# ai_hub_usb.net
KiCad netlist of a schematic drawn in EAGLE
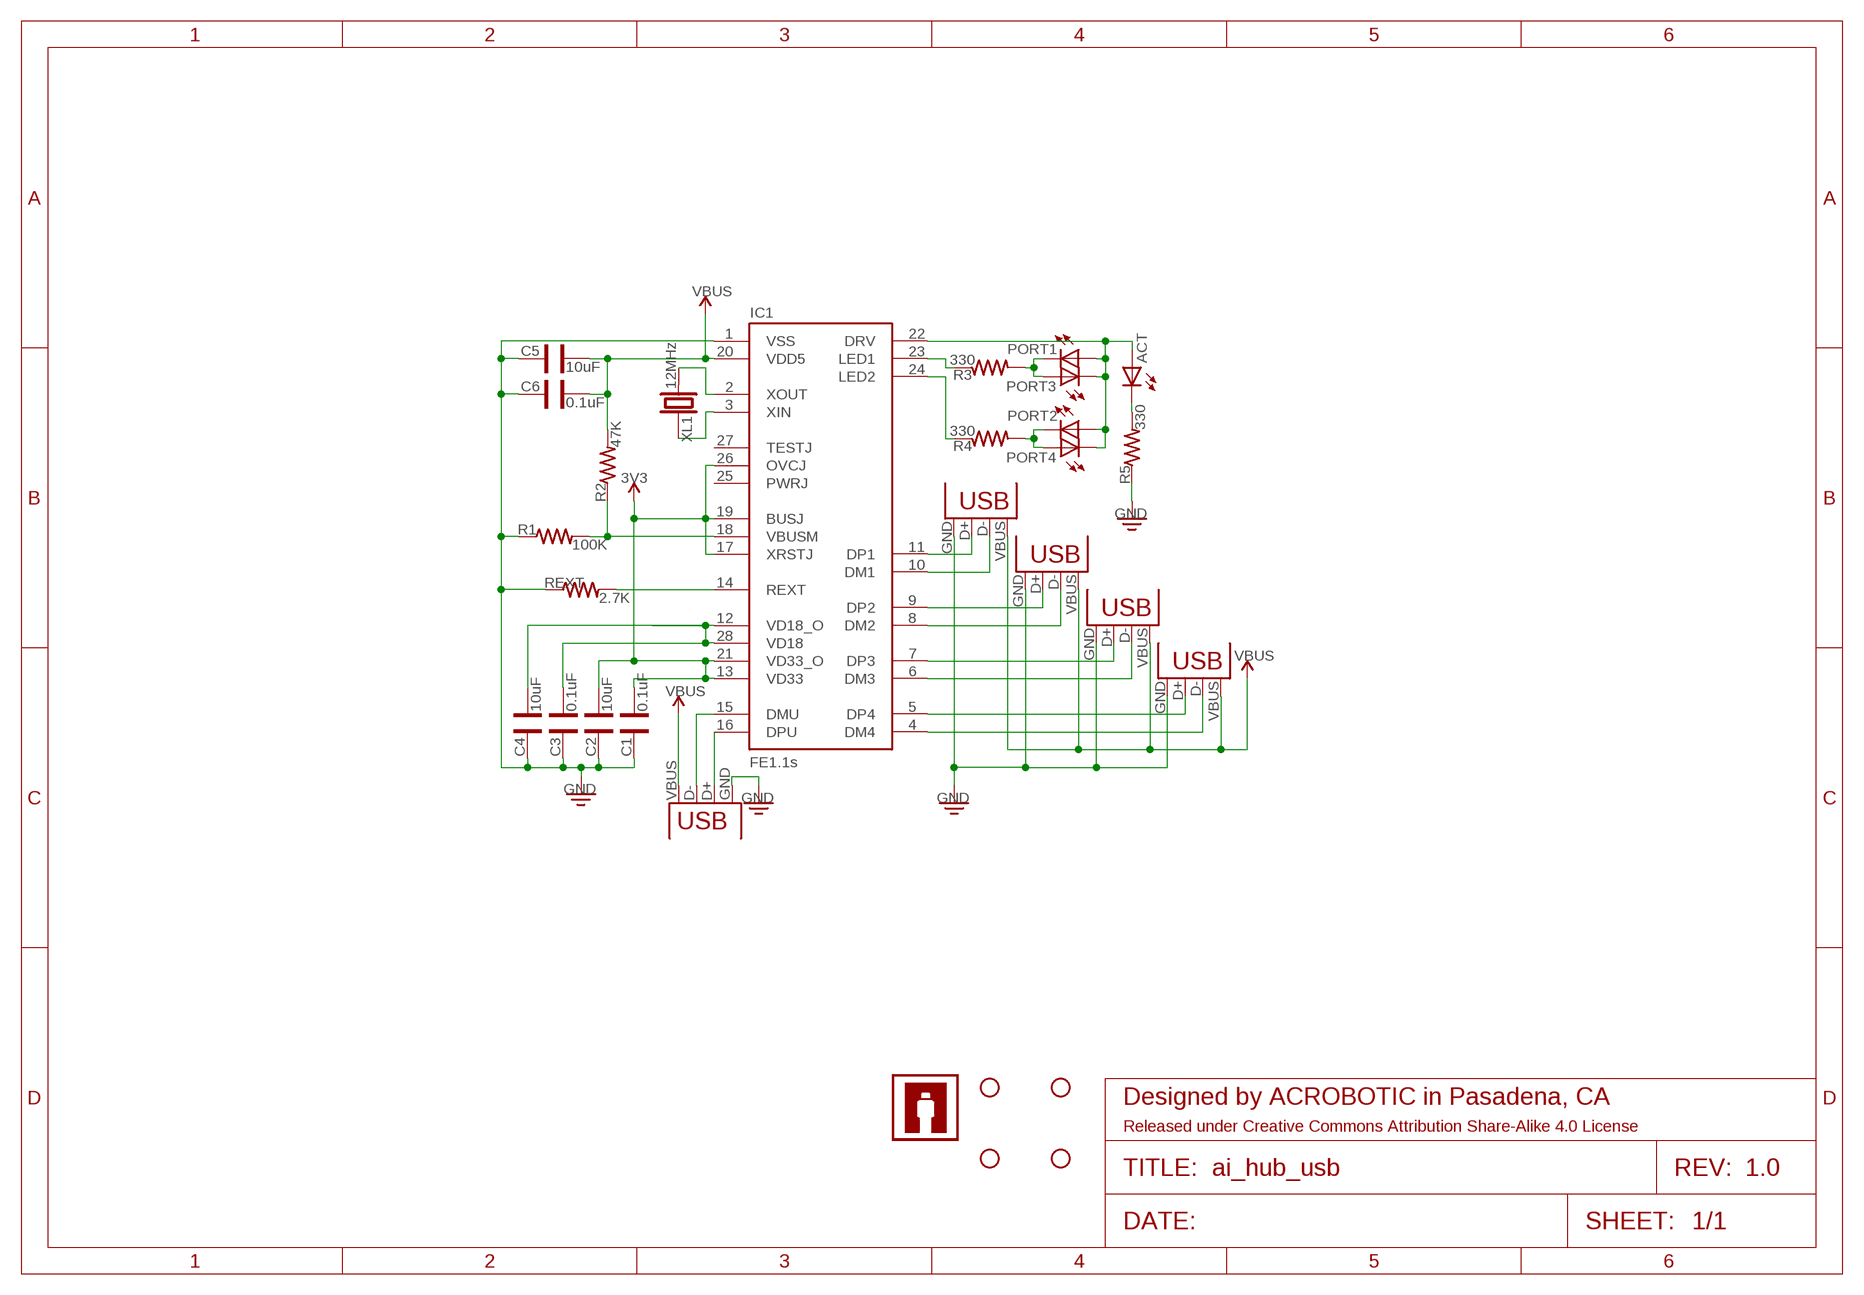
[diagram p0: schematic, sheet 1]

(export (version "E")
  (design (tool "Eeschema 10.0.6"))
  (components
    (comp (ref "ACT")
      (value "LED0603")
      (footprint "eagle-import:LED-0603")
      (libsource (lib "eagle-import") (part "LED0603"))
    )
    (comp (ref "C1")
      (value "0.1uF")
      (footprint "eagle-import:CAP-0603")
      (libsource (lib "eagle-import") (part "CAP0603"))
    )
    (comp (ref "C2")
      (value "10uF")
      (footprint "eagle-import:CAP-0603")
      (libsource (lib "eagle-import") (part "CAP0603"))
    )
    (comp (ref "C3")
      (value "0.1uF")
      (footprint "eagle-import:CAP-0603")
      (libsource (lib "eagle-import") (part "CAP0603"))
    )
    (comp (ref "C4")
      (value "10uF")
      (footprint "eagle-import:CAP-0603")
      (libsource (lib "eagle-import") (part "CAP0603"))
    )
    (comp (ref "C5")
      (value "10uF")
      (footprint "eagle-import:CAP-0603")
      (libsource (lib "eagle-import") (part "CAP0603"))
    )
    (comp (ref "C6")
      (value "0.1uF")
      (footprint "eagle-import:CAP-0603")
      (libsource (lib "eagle-import") (part "CAP0603"))
    )
    (comp (ref "FRAME1")
      (value "FRAME-LETTER")
      (footprint "eagle-import:CREATIVE-COMMONS")
      (fields (field (name "REV") "1.0"))
      (libsource (lib "eagle-import") (part "FRAME-LETTER"))
    )
    (comp (ref "IC1")
      (value "FE1.1S")
      (footprint "eagle-import:FE1.1S_SSOP-28")
      (libsource (lib "eagle-import") (part "FE1.1S"))
    )
    (comp (ref "PORT1")
      (value "LED0603")
      (footprint "eagle-import:LED-0603")
      (libsource (lib "eagle-import") (part "LED0603"))
    )
    (comp (ref "PORT2")
      (value "LED0603")
      (footprint "eagle-import:LED-0603")
      (libsource (lib "eagle-import") (part "LED0603"))
    )
    (comp (ref "PORT3")
      (value "LED0603")
      (footprint "eagle-import:LED-0603")
      (libsource (lib "eagle-import") (part "LED0603"))
    )
    (comp (ref "PORT4")
      (value "LED0603")
      (footprint "eagle-import:LED-0603")
      (libsource (lib "eagle-import") (part "LED0603"))
    )
    (comp (ref "R1")
      (value "100K")
      (footprint "eagle-import:RES-0603")
      (libsource (lib "eagle-import") (part "RES0603"))
    )
    (comp (ref "R2")
      (value "47K")
      (footprint "eagle-import:RES-0603")
      (libsource (lib "eagle-import") (part "RES0603"))
    )
    (comp (ref "R3")
      (value "330")
      (footprint "eagle-import:RES-0603")
      (libsource (lib "eagle-import") (part "RES0603"))
    )
    (comp (ref "R4")
      (value "330")
      (footprint "eagle-import:RES-0603")
      (libsource (lib "eagle-import") (part "RES0603"))
    )
    (comp (ref "R5")
      (value "330")
      (footprint "eagle-import:RES-0603")
      (libsource (lib "eagle-import") (part "RES0603"))
    )
    (comp (ref "REXT")
      (value "2.7K")
      (footprint "eagle-import:RES-0603")
      (libsource (lib "eagle-import") (part "RES0603"))
    )
    (comp (ref "STANDOFF1")
      (value "STAND-OFF4")
      (footprint "eagle-import:STAND-OFF-4")
      (libsource (lib "eagle-import") (part "STAND-OFF4"))
    )
    (comp (ref "STANDOFF2")
      (value "STAND-OFF4")
      (footprint "eagle-import:STAND-OFF-4")
      (libsource (lib "eagle-import") (part "STAND-OFF4"))
    )
    (comp (ref "STANDOFF3")
      (value "STAND-OFF4")
      (footprint "eagle-import:STAND-OFF-4")
      (libsource (lib "eagle-import") (part "STAND-OFF4"))
    )
    (comp (ref "STANDOFF4")
      (value "STAND-OFF4")
      (footprint "eagle-import:STAND-OFF-4")
      (libsource (lib "eagle-import") (part "STAND-OFF4"))
    )
    (comp (ref "U$5")
      (value "AI-LOGOXS")
      (footprint "eagle-import:AI-LOGO-XS")
      (libsource (lib "eagle-import") (part "AI-LOGOXS"))
    )
    (comp (ref "U$6")
      (value "AI-LOGOXS")
      (footprint "eagle-import:AI-LOGO-XS")
      (libsource (lib "eagle-import") (part "AI-LOGOXS"))
    )
    (comp (ref "USB1")
      (value "USBMICROB-PTH")
      (footprint "eagle-import:USB-MICROB-TH")
      (libsource (lib "eagle-import") (part "USBMICROB-PTH"))
    )
    (comp (ref "USB2")
      (value "USBA-PTH")
      (footprint "eagle-import:USB-A-F-PTH")
      (libsource (lib "eagle-import") (part "USBA-PTH"))
    )
    (comp (ref "USB3")
      (value "USBA-PTH")
      (footprint "eagle-import:USB-A-F-PTH")
      (libsource (lib "eagle-import") (part "USBA-PTH"))
    )
    (comp (ref "USB4")
      (value "USBA-PTH")
      (footprint "eagle-import:USB-A-F-PTH")
      (libsource (lib "eagle-import") (part "USBA-PTH"))
    )
    (comp (ref "USB5")
      (value "USBA-PTH")
      (footprint "eagle-import:USB-A-F-PTH")
      (libsource (lib "eagle-import") (part "USBA-PTH"))
    )
    (comp (ref "XL1")
      (value "12MHz")
      (footprint "eagle-import:HC49UP")
      (libsource (lib "eagle-import") (part "CRYSTALHC49UP"))
    )
  )
  (nets
    (net (code "1") (name "3V3") (class "Default")
      (node (ref "C1") (pin "1") (pinfunction "1_1") (pintype "passive"))
      (node (ref "C2") (pin "1") (pinfunction "1_1") (pintype "passive"))
      (node (ref "IC1") (pin "13") (pinfunction "VD33_13") (pintype "bidirectional"))
      (node (ref "IC1") (pin "17") (pinfunction "XRSTJ_17") (pintype "bidirectional"))
      (node (ref "IC1") (pin "19") (pinfunction "BUSJ_19") (pintype "bidirectional"))
      (node (ref "IC1") (pin "21") (pinfunction "VD33_O_21") (pintype "bidirectional"))
      (node (ref "IC1") (pin "26") (pinfunction "OVCJ_26") (pintype "bidirectional"))
    )
    (net (code "2") (name "GND") (class "Default")
      (node (ref "C1") (pin "2") (pinfunction "2_2") (pintype "passive"))
      (node (ref "C2") (pin "2") (pinfunction "2_2") (pintype "passive"))
      (node (ref "C3") (pin "2") (pinfunction "2_2") (pintype "passive"))
      (node (ref "C4") (pin "2") (pinfunction "2_2") (pintype "passive"))
      (node (ref "C5") (pin "2") (pinfunction "2_2") (pintype "passive"))
      (node (ref "C6") (pin "2") (pinfunction "2_2") (pintype "passive"))
      (node (ref "IC1") (pin "1") (pinfunction "VSS_1") (pintype "bidirectional"))
      (node (ref "R1") (pin "1") (pinfunction "1_1") (pintype "passive"))
      (node (ref "R5") (pin "1") (pinfunction "1_1") (pintype "passive"))
      (node (ref "REXT") (pin "1") (pinfunction "1_1") (pintype "passive"))
      (node (ref "USB1") (pin "GND") (pinfunction "GND_GND") (pintype "bidirectional"))
      (node (ref "USB2") (pin "GND") (pinfunction "GND_GND") (pintype "bidirectional"))
      (node (ref "USB3") (pin "GND") (pinfunction "GND_GND") (pintype "bidirectional"))
      (node (ref "USB4") (pin "GND") (pinfunction "GND_GND") (pintype "bidirectional"))
      (node (ref "USB5") (pin "GND") (pinfunction "GND_GND") (pintype "bidirectional"))
    )
    (net (code "3") (name "Net-(ACT-PadC)") (class "Default")
      (node (ref "ACT") (pin "C") (pinfunction "C_C") (pintype "passive"))
      (node (ref "R5") (pin "2") (pinfunction "2_2") (pintype "passive"))
    )
    (net (code "4") (name "Net-(IC1-DM1)") (class "Default")
      (node (ref "IC1") (pin "10") (pinfunction "DM1_10") (pintype "bidirectional"))
      (node (ref "USB5") (pin "D-") (pinfunction "D-_D-") (pintype "bidirectional"))
    )
    (net (code "5") (name "Net-(IC1-DM2)") (class "Default")
      (node (ref "IC1") (pin "8") (pinfunction "DM2_8") (pintype "bidirectional"))
      (node (ref "USB4") (pin "D-") (pinfunction "D-_D-") (pintype "bidirectional"))
    )
    (net (code "6") (name "Net-(IC1-DM3)") (class "Default")
      (node (ref "IC1") (pin "6") (pinfunction "DM3_6") (pintype "bidirectional"))
      (node (ref "USB3") (pin "D-") (pinfunction "D-_D-") (pintype "bidirectional"))
    )
    (net (code "7") (name "Net-(IC1-DM4)") (class "Default")
      (node (ref "IC1") (pin "4") (pinfunction "DM4_4") (pintype "bidirectional"))
      (node (ref "USB2") (pin "D-") (pinfunction "D-_D-") (pintype "bidirectional"))
    )
    (net (code "8") (name "Net-(IC1-DMU)") (class "Default")
      (node (ref "IC1") (pin "15") (pinfunction "DMU_15") (pintype "bidirectional"))
      (node (ref "USB1") (pin "D-") (pinfunction "D-_D-") (pintype "bidirectional"))
    )
    (net (code "9") (name "Net-(IC1-DP1)") (class "Default")
      (node (ref "IC1") (pin "11") (pinfunction "DP1_11") (pintype "bidirectional"))
      (node (ref "USB5") (pin "D+") (pinfunction "D+_D+") (pintype "bidirectional"))
    )
    (net (code "10") (name "Net-(IC1-DP2)") (class "Default")
      (node (ref "IC1") (pin "9") (pinfunction "DP2_9") (pintype "bidirectional"))
      (node (ref "USB4") (pin "D+") (pinfunction "D+_D+") (pintype "bidirectional"))
    )
    (net (code "11") (name "Net-(IC1-DP3)") (class "Default")
      (node (ref "IC1") (pin "7") (pinfunction "DP3_7") (pintype "bidirectional"))
      (node (ref "USB3") (pin "D+") (pinfunction "D+_D+") (pintype "bidirectional"))
    )
    (net (code "12") (name "Net-(IC1-DP4)") (class "Default")
      (node (ref "IC1") (pin "5") (pinfunction "DP4_5") (pintype "bidirectional"))
      (node (ref "USB2") (pin "D+") (pinfunction "D+_D+") (pintype "bidirectional"))
    )
    (net (code "13") (name "Net-(IC1-DPU)") (class "Default")
      (node (ref "IC1") (pin "16") (pinfunction "DPU_16") (pintype "bidirectional"))
      (node (ref "USB1") (pin "D+") (pinfunction "D+_D+") (pintype "bidirectional"))
    )
    (net (code "14") (name "Net-(IC1-DRV)") (class "Default")
      (node (ref "ACT") (pin "A") (pinfunction "A_A") (pintype "passive"))
      (node (ref "IC1") (pin "22") (pinfunction "DRV_22") (pintype "bidirectional"))
      (node (ref "PORT1") (pin "A") (pinfunction "A_A") (pintype "passive"))
      (node (ref "PORT2") (pin "A") (pinfunction "A_A") (pintype "passive"))
      (node (ref "PORT3") (pin "C") (pinfunction "C_C") (pintype "passive"))
      (node (ref "PORT4") (pin "C") (pinfunction "C_C") (pintype "passive"))
    )
    (net (code "15") (name "Net-(IC1-LED1)") (class "Default")
      (node (ref "IC1") (pin "23") (pinfunction "LED1_23") (pintype "bidirectional"))
      (node (ref "R3") (pin "1") (pinfunction "1_1") (pintype "passive"))
    )
    (net (code "16") (name "Net-(IC1-LED2)") (class "Default")
      (node (ref "IC1") (pin "24") (pinfunction "LED2_24") (pintype "bidirectional"))
      (node (ref "R4") (pin "1") (pinfunction "1_1") (pintype "passive"))
    )
    (net (code "17") (name "Net-(IC1-REXT)") (class "Default")
      (node (ref "IC1") (pin "14") (pinfunction "REXT_14") (pintype "bidirectional"))
      (node (ref "REXT") (pin "2") (pinfunction "2_2") (pintype "passive"))
    )
    (net (code "18") (name "Net-(IC1-VBUSM)") (class "Default")
      (node (ref "IC1") (pin "18") (pinfunction "VBUSM_18") (pintype "bidirectional"))
      (node (ref "R1") (pin "2") (pinfunction "2_2") (pintype "passive"))
      (node (ref "R2") (pin "1") (pinfunction "1_1") (pintype "passive"))
    )
    (net (code "19") (name "Net-(IC1-VD18)") (class "Default")
      (node (ref "C3") (pin "1") (pinfunction "1_1") (pintype "passive"))
      (node (ref "C4") (pin "1") (pinfunction "1_1") (pintype "passive"))
      (node (ref "IC1") (pin "12") (pinfunction "VD18_O_12") (pintype "bidirectional"))
      (node (ref "IC1") (pin "28") (pinfunction "VD18_28") (pintype "bidirectional"))
    )
    (net (code "20") (name "Net-(IC1-XIN)") (class "Default")
      (node (ref "IC1") (pin "3") (pinfunction "XIN_3") (pintype "bidirectional"))
      (node (ref "XL1") (pin "1") (pinfunction "1_1") (pintype "passive"))
    )
    (net (code "21") (name "Net-(IC1-XOUT)") (class "Default")
      (node (ref "IC1") (pin "2") (pinfunction "XOUT_2") (pintype "bidirectional"))
      (node (ref "XL1") (pin "2") (pinfunction "2_2") (pintype "passive"))
    )
    (net (code "22") (name "Net-(PORT1-PadC)") (class "Default")
      (node (ref "PORT1") (pin "C") (pinfunction "C_C") (pintype "passive"))
      (node (ref "PORT3") (pin "A") (pinfunction "A_A") (pintype "passive"))
      (node (ref "R3") (pin "2") (pinfunction "2_2") (pintype "passive"))
    )
    (net (code "23") (name "Net-(PORT2-PadC)") (class "Default")
      (node (ref "PORT2") (pin "C") (pinfunction "C_C") (pintype "passive"))
      (node (ref "PORT4") (pin "A") (pinfunction "A_A") (pintype "passive"))
      (node (ref "R4") (pin "2") (pinfunction "2_2") (pintype "passive"))
    )
    (net (code "24") (name "VBUS") (class "Default")
      (node (ref "C5") (pin "1") (pinfunction "1_1") (pintype "passive"))
      (node (ref "C6") (pin "1") (pinfunction "1_1") (pintype "passive"))
      (node (ref "IC1") (pin "20") (pinfunction "VDD5_20") (pintype "bidirectional"))
      (node (ref "R2") (pin "2") (pinfunction "2_2") (pintype "passive"))
      (node (ref "USB1") (pin "VBUS") (pinfunction "VBUS_VBUS") (pintype "bidirectional"))
      (node (ref "USB2") (pin "VBUS") (pinfunction "VBUS_VBUS") (pintype "bidirectional"))
      (node (ref "USB3") (pin "VBUS") (pinfunction "VBUS_VBUS") (pintype "bidirectional"))
      (node (ref "USB4") (pin "VBUS") (pinfunction "VBUS_VBUS") (pintype "bidirectional"))
      (node (ref "USB5") (pin "VBUS") (pinfunction "VBUS_VBUS") (pintype "bidirectional"))
    )
    (net (code "25") (name "unconnected-(IC1-PWRJ-Pad25)") (class "Default")
      (node (ref "IC1") (pin "25") (pinfunction "PWRJ_25") (pintype "bidirectional"))
    )
    (net (code "26") (name "unconnected-(IC1-TESTJ-Pad27)") (class "Default")
      (node (ref "IC1") (pin "27") (pinfunction "TESTJ_27") (pintype "bidirectional"))
    )
  )
)
